# FPGA_PWRIN.net
KiCad netlist of a schematic drawn in Altium Designer
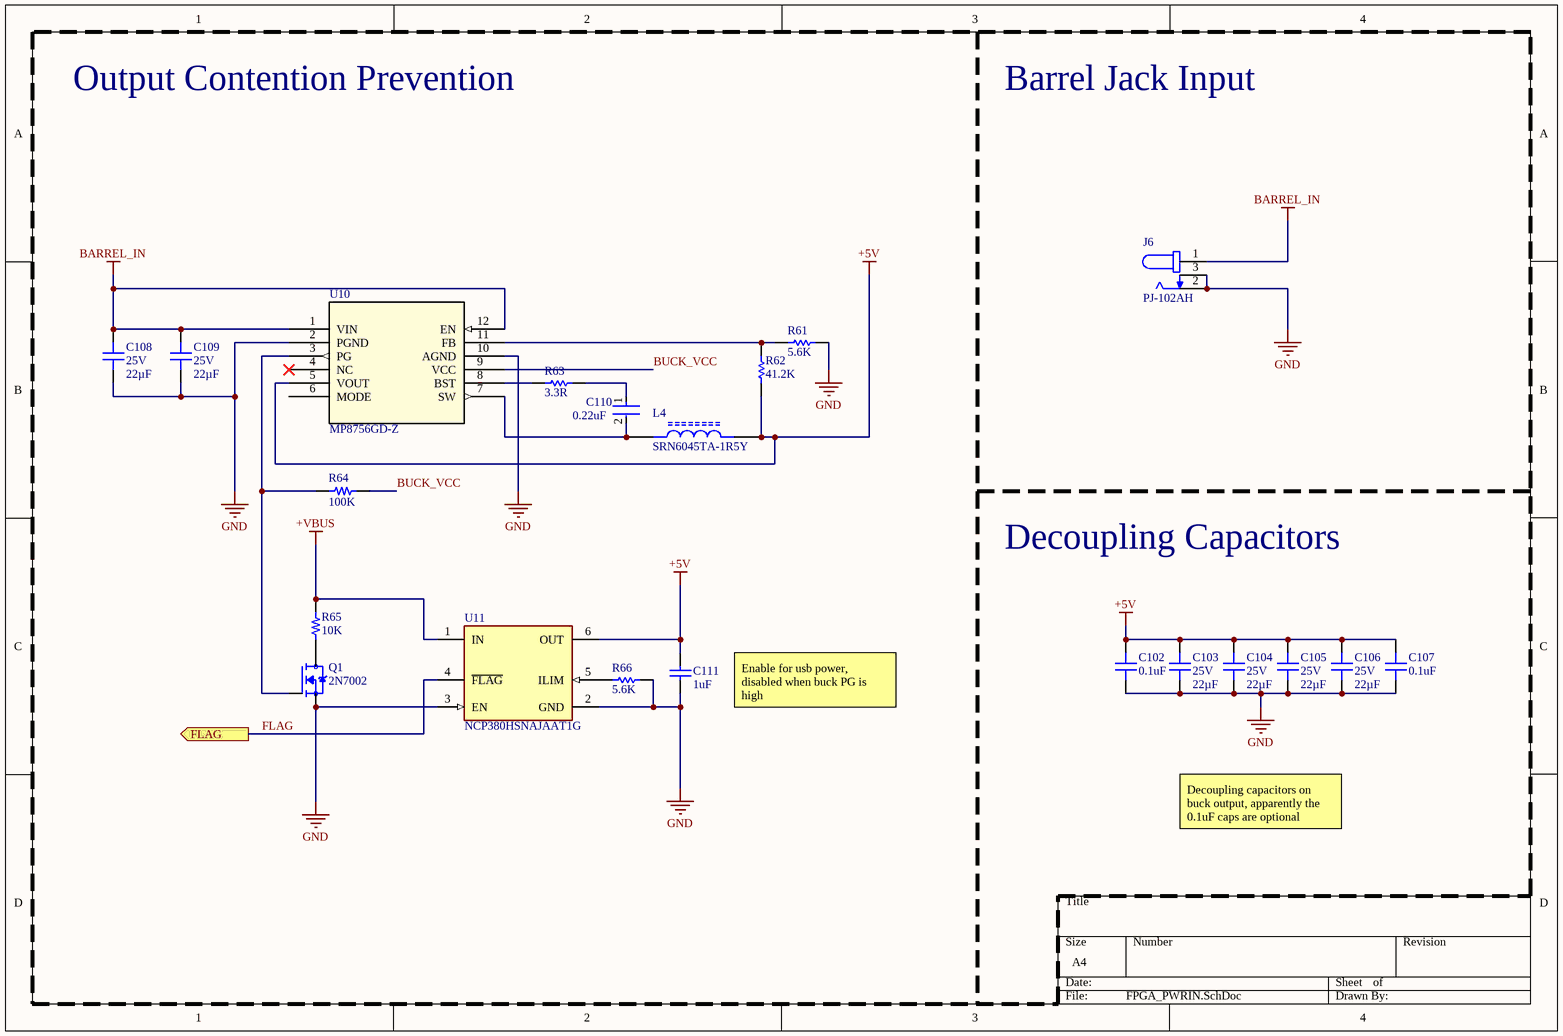
[diagram p0: FPGA_PWRIN.SchDoc]

(export (version "E")
  (design (tool "Eeschema 10.0.6"))
  (components
    (comp (ref "C102")
      (value "CAP CER 0.1UF 100V 10% X7R 0603")
      (footprint "CAP 0603_1608")
      (fields (field (name "CAPACITANCE") "0.1uF") (field (name "TOLERANCE") "10%"))
      (libsource (lib "Midnight Sun") (part "Capacitor"))
    )
    (comp (ref "C103")
      (value "CAP CER 22UF 25V X5R 0805")
      (footprint "CAP 0805_2012")
      (description "22 µF ±20% 25V Ceramic Capacitor X5R 0805 (2012 Metric)")
      (fields
        (field (name "VOLTAGE RATING") "25V")
        (field (name "CAPACITANCE") "22µF")
        (field (name "TOLERANCE") "20%")
      )
      (libsource (lib "Midnight Sun") (part "Capacitor"))
    )
    (comp (ref "C104")
      (value "CAP CER 22UF 25V X5R 0805")
      (footprint "CAP 0805_2012")
      (description "22 µF ±20% 25V Ceramic Capacitor X5R 0805 (2012 Metric)")
      (fields
        (field (name "VOLTAGE RATING") "25V")
        (field (name "CAPACITANCE") "22µF")
        (field (name "TOLERANCE") "20%")
      )
      (libsource (lib "Midnight Sun") (part "Capacitor"))
    )
    (comp (ref "C105")
      (value "CAP CER 22UF 25V X5R 0805")
      (footprint "CAP 0805_2012")
      (description "22 µF ±20% 25V Ceramic Capacitor X5R 0805 (2012 Metric)")
      (fields
        (field (name "VOLTAGE RATING") "25V")
        (field (name "CAPACITANCE") "22µF")
        (field (name "TOLERANCE") "20%")
      )
      (libsource (lib "Midnight Sun") (part "Capacitor"))
    )
    (comp (ref "C106")
      (value "CAP CER 22UF 25V X5R 0805")
      (footprint "CAP 0805_2012")
      (description "22 µF ±20% 25V Ceramic Capacitor X5R 0805 (2012 Metric)")
      (fields
        (field (name "VOLTAGE RATING") "25V")
        (field (name "CAPACITANCE") "22µF")
        (field (name "TOLERANCE") "20%")
      )
      (libsource (lib "Midnight Sun") (part "Capacitor"))
    )
    (comp (ref "C107")
      (value "CAP CER 0.1UF 100V 10% X7R 0603")
      (footprint "CAP 0603_1608")
      (fields (field (name "CAPACITANCE") "0.1uF") (field (name "TOLERANCE") "10%"))
      (libsource (lib "Midnight Sun") (part "Capacitor"))
    )
    (comp (ref "C108")
      (value "CAP CER 22UF 25V X5R 0805")
      (footprint "CAP 0805_2012")
      (description "22 µF ±20% 25V Ceramic Capacitor X5R 0805 (2012 Metric)")
      (fields
        (field (name "VOLTAGE RATING") "25V")
        (field (name "CAPACITANCE") "22µF")
        (field (name "TOLERANCE") "20%")
      )
      (libsource (lib "Midnight Sun") (part "Capacitor"))
    )
    (comp (ref "C109")
      (value "CAP CER 22UF 25V X5R 0805")
      (footprint "CAP 0805_2012")
      (description "22 µF ±20% 25V Ceramic Capacitor X5R 0805 (2012 Metric)")
      (fields
        (field (name "VOLTAGE RATING") "25V")
        (field (name "CAPACITANCE") "22µF")
        (field (name "TOLERANCE") "20%")
      )
      (libsource (lib "Midnight Sun") (part "Capacitor"))
    )
    (comp (ref "C110")
      (value "0.22uF")
      (footprint "FP-GCM188-0_1-IPC_B")
      (description "Ceramic Capacitor for Automotive 220nF  ±10% 25VDC X7R 0603 Paper T/R")
      (fields (field (name "TOLERANCE") "10%"))
      (libsource (lib "Altium Content Vault") (part "02cd4be3c70576c341d710602a673aa"))
    )
    (comp (ref "C111")
      (value "1uF")
      (footprint "CAPC1005X55X25LL05T10")
      (fields (field (name "MANUFACTURER") "Murata") (field (name "PART NUMBER") "GRM155R71C104KA88J"))
      (libsource (lib "BIG_FPGA") (part "CMP-2008-03928-1"))
    )
    (comp (ref "J6")
      (value "PJ-102AH")
      (footprint "CUI_PJ-102AH")
      (description "2.0 mm Center Pin, 5.0 A, Right Angle, Through Hole, Tapered Pins, Dc Power Jack Connector")
      (libsource (lib "BIG_FPGA") (part "PJ-102AH"))
    )
    (comp (ref "L4")
      (value "SRN6045TA-1R5Y")
      (footprint "IND_SRN6045TA-1R5Y")
      (libsource (lib "BIG_FPGA") (part "SRN6045TA-1R5Y"))
    )
    (comp (ref "Q1")
      (value "2N7002")
      (footprint "SOT95P240X111-3N")
      (description "N-Channel 60V 280mA (Ta) 350mW (Ta) Surface Mount SOT-23-3 (TO-236)")
      (fields (field (name "MP") "altium_native_batch"))
      (libsource (lib "BIG_FPGA") (part "2N7002"))
    )
    (comp (ref "R61")
      (value "5.6K")
      (footprint "RESC1608X55X25NL10T15")
      (description "Chip Resistor, 5.6 KOhm, +/- 1%, 0.1 W, -55 to 155 degC, 0603 (1608 Metric), RoHS, Tape and Reel")
      (fields (field (name "TOLERANCE") "1%"))
      (libsource (lib "Altium Content Vault") (part "RES-2"))
    )
    (comp (ref "R62")
      (value "41.2K")
      (footprint "RESC1608X55X30LL20T20")
      (fields (field (name "MANUFACTURER") "Panasonic") (field (name "PART NUMBER") "ERA3AEB4122V"))
      (libsource (lib "Altium Content Vault") (part "RES"))
    )
    (comp (ref "R63")
      (value "3.3R")
      (footprint "RESC1608X55X25ML10T15")
      (fields (field (name "PART NUMBER") "RC0603JR-073R3L") (field (name "MANUFACTURER") "Yageo"))
      (libsource (lib "Altium Content Vault") (part "RES"))
    )
    (comp (ref "R64")
      (value "100K")
      (footprint "RES 0603_1608")
      (description "100 ±1% 0.1W, 1/10W Chip Resistor 0603 (1608 Metric) Automotive AEC-Q200 Thick Film")
      (libsource (lib "Midnight Sun") (part "Resistor"))
    )
    (comp (ref "R65")
      (value "10K")
      (footprint "RES 0603_1608")
      (description "10 ±1% 0.1W, 1/10W Chip Resistor 0603 (1608 Metric) Automotive AEC-Q200 Thick Film")
      (libsource (lib "Midnight Sun") (part "Resistor"))
    )
    (comp (ref "R66")
      (value "5.6K")
      (footprint "RESC1608X55X25NL10T15")
      (description "Chip Resistor, 5.6 KOhm, +/- 1%, 0.1 W, -55 to 155 degC, 0603 (1608 Metric), RoHS, Tape and Reel")
      (fields (field (name "TOLERANCE") "1%"))
      (libsource (lib "Altium Content Vault") (part "RES-2"))
    )
    (comp (ref "U10")
      (value "MP8756GD-Z")
      (footprint "QFN-12_MP8756_MNP")
      (description "No Description Available")
      (libsource (lib "BIG_FPGA") (part "MP8756GD-Z"))
    )
    (comp (ref "U11")
      (value "NCP380HSNAJAAT1G")
      (footprint "FP-318G-02-MFG")
      (description "IC PWR SWITCH P-CHAN 1:1 6TSOP")
      (fields
        (field (name "OCTOPART") "https://octopart.com/ncp380hsnajaat1g-on+semiconductor-19977073")
        (field (name "MANUFACTURER") "ON Semiconductor")
      )
      (libsource (lib "Altium Content Vault") (part "4627b8c5534bba069baadb8d8a2e8b9"))
    )
  )
  (nets
    (net (code "1") (name "+5V") (class "Default")
      (node (ref "C102") (pin "1") (pinfunction "1_1") (pintype "passive"))
      (node (ref "C103") (pin "2") (pinfunction "2_2") (pintype "passive"))
      (node (ref "C104") (pin "2") (pinfunction "2_2") (pintype "passive"))
      (node (ref "C105") (pin "2") (pinfunction "2_2") (pintype "passive"))
      (node (ref "C106") (pin "2") (pinfunction "2_2") (pintype "passive"))
      (node (ref "C107") (pin "1") (pinfunction "1_1") (pintype "passive"))
      (node (ref "C111") (pin "2") (pinfunction "2_2") (pintype "passive"))
      (node (ref "L4") (pin "2") (pinfunction "2_2") (pintype "passive"))
      (node (ref "R62") (pin "1") (pinfunction "1_1") (pintype "passive"))
      (node (ref "U10") (pin "5") (pinfunction "VOUT_5") (pintype "power_in"))
      (node (ref "U11") (pin "6") (pinfunction "OUT_6") (pintype "power_in"))
    )
    (net (code "2") (name "+VBUS") (class "Default")
      (node (ref "R65") (pin "1") (pinfunction "1_1") (pintype "passive"))
      (node (ref "U11") (pin "1") (pinfunction "IN_1") (pintype "power_in"))
    )
    (net (code "3") (name "/BUCK_VCC") (class "Default")
      (node (ref "R64") (pin "2") (pinfunction "2_2") (pintype "passive"))
      (node (ref "U10") (pin "9") (pinfunction "VCC_9") (pintype "power_in"))
    )
    (net (code "4") (name "/FLAG") (class "Default")
      (node (ref "U11") (pin "4") (pinfunction "~{FLAG}_4") (pintype "open_collector"))
    )
    (net (code "5") (name "BARREL_IN") (class "Default")
      (node (ref "C108") (pin "2") (pinfunction "2_2") (pintype "passive"))
      (node (ref "C109") (pin "2") (pinfunction "2_2") (pintype "passive"))
      (node (ref "J6") (pin "1") (pinfunction "1_1") (pintype "passive"))
      (node (ref "U10") (pin "1") (pinfunction "VIN_1") (pintype "power_in"))
      (node (ref "U10") (pin "12") (pinfunction "EN_12") (pintype "input"))
    )
    (net (code "6") (name "GND") (class "Default")
      (node (ref "C102") (pin "2") (pinfunction "2_2") (pintype "passive"))
      (node (ref "C103") (pin "1") (pinfunction "1_1") (pintype "passive"))
      (node (ref "C104") (pin "1") (pinfunction "1_1") (pintype "passive"))
      (node (ref "C105") (pin "1") (pinfunction "1_1") (pintype "passive"))
      (node (ref "C106") (pin "1") (pinfunction "1_1") (pintype "passive"))
      (node (ref "C107") (pin "2") (pinfunction "2_2") (pintype "passive"))
      (node (ref "C108") (pin "1") (pinfunction "1_1") (pintype "passive"))
      (node (ref "C109") (pin "1") (pinfunction "1_1") (pintype "passive"))
      (node (ref "C111") (pin "1") (pinfunction "1_1") (pintype "passive"))
      (node (ref "J6") (pin "2") (pinfunction "2_2") (pintype "passive"))
      (node (ref "J6") (pin "3") (pinfunction "3_3") (pintype "passive"))
      (node (ref "Q1") (pin "2") (pinfunction "S_2") (pintype "passive"))
      (node (ref "R61") (pin "1") (pinfunction "1_1") (pintype "passive"))
      (node (ref "R66") (pin "1") (pinfunction "1_1") (pintype "passive"))
      (node (ref "U10") (pin "10") (pinfunction "AGND_10") (pintype "power_in"))
      (node (ref "U10") (pin "2") (pinfunction "PGND_2") (pintype "power_in"))
      (node (ref "U11") (pin "2") (pinfunction "GND_2") (pintype "power_in"))
      (node (ref "U11") (pin "3") (pinfunction "EN_3") (pintype "input"))
    )
    (net (code "7") (name "Net-(C110-Pad1)") (class "Default")
      (node (ref "C110") (pin "1") (pinfunction "1_1") (pintype "passive"))
      (node (ref "R63") (pin "2") (pinfunction "2_2") (pintype "passive"))
    )
    (net (code "8") (name "Net-(Q1-D)") (class "Default")
      (node (ref "Q1") (pin "3") (pinfunction "D_3") (pintype "passive"))
      (node (ref "R65") (pin "2") (pinfunction "2_2") (pintype "passive"))
    )
    (net (code "9") (name "Net-(Q1-G)") (class "Default")
      (node (ref "Q1") (pin "1") (pinfunction "G_1") (pintype "passive"))
      (node (ref "R64") (pin "1") (pinfunction "1_1") (pintype "passive"))
      (node (ref "U10") (pin "3") (pinfunction "PG_3") (pintype "output"))
    )
    (net (code "10") (name "Net-(U10-BST)") (class "Default")
      (node (ref "R63") (pin "1") (pinfunction "1_1") (pintype "passive"))
      (node (ref "U10") (pin "8") (pinfunction "BST_8") (pintype "power_in"))
    )
    (net (code "11") (name "Net-(U10-FB)") (class "Default")
      (node (ref "R61") (pin "2") (pinfunction "2_2") (pintype "passive"))
      (node (ref "R62") (pin "2") (pinfunction "2_2") (pintype "passive"))
      (node (ref "U10") (pin "11") (pinfunction "FB_11") (pintype "passive"))
    )
    (net (code "12") (name "Net-(U10-SW)") (class "Default")
      (node (ref "C110") (pin "2") (pinfunction "2_2") (pintype "passive"))
      (node (ref "L4") (pin "1") (pinfunction "1_1") (pintype "passive"))
      (node (ref "U10") (pin "7") (pinfunction "SW_7") (pintype "output"))
    )
    (net (code "13") (name "Net-(U11-ILIM)") (class "Default")
      (node (ref "R66") (pin "2") (pinfunction "2_2") (pintype "passive"))
      (node (ref "U11") (pin "5") (pinfunction "ILIM_5") (pintype "input"))
    )
    (net (code "14") (name "unconnected-(U10-MODE-Pad6)") (class "Default")
      (node (ref "U10") (pin "6") (pinfunction "MODE_6") (pintype "passive"))
    )
    (net (code "15") (name "unconnected-(U10-NC-Pad4)") (class "Default")
      (node (ref "U10") (pin "4") (pinfunction "NC_4") (pintype "passive+no_connect"))
    )
  )
)
